# H-00488_-_I2C_Address.net
KiCad netlist of a schematic drawn in Altium Designer
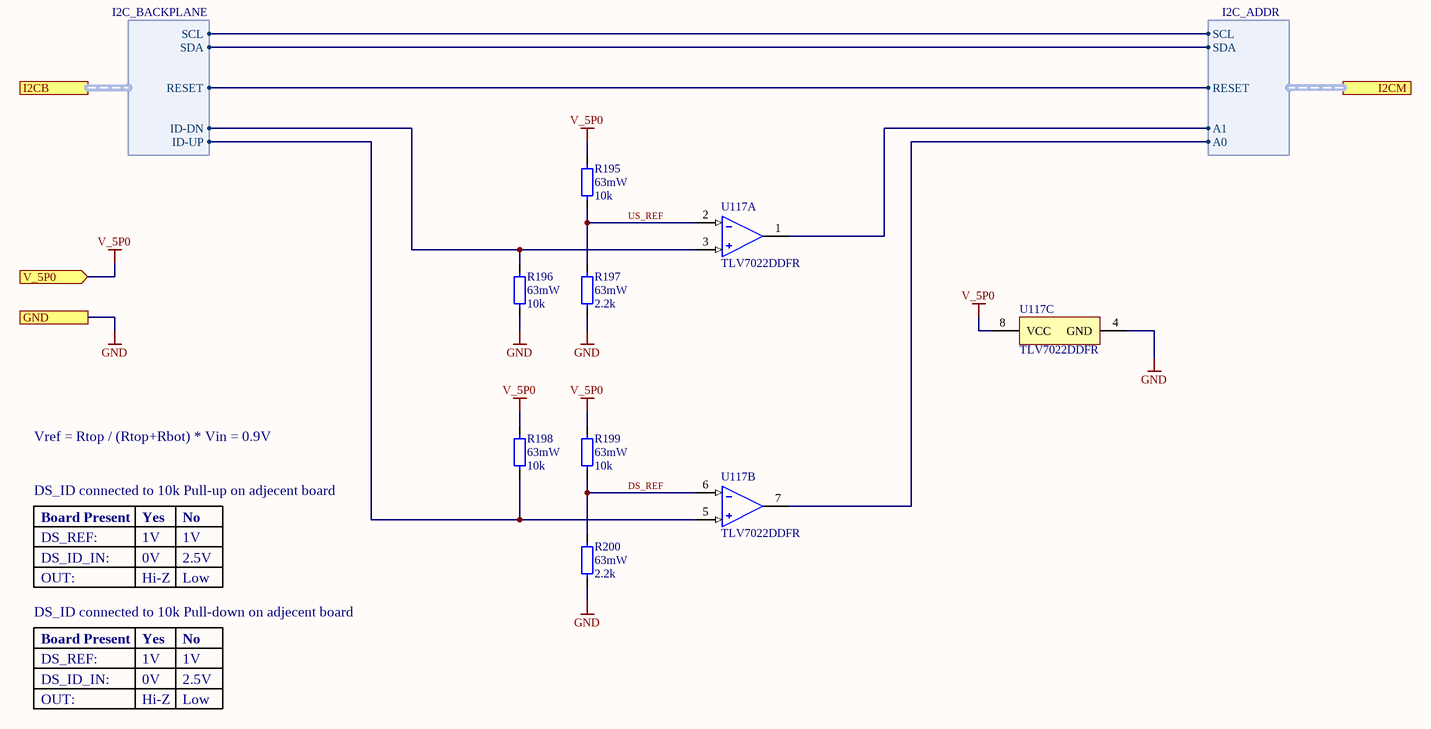
[diagram p0: H-00488 - I2C Address.SchDoc]

(export (version "E")
  (design (tool "Eeschema 10.0.6"))
  (components
    (comp (ref "R195")
      (value "10k")
      (footprint "RESC100X50X40L25N")
      (description "RES Standard Thick Film 0402 10K0 ±1% 0,063W")
      (fields
        (field (name "TOLERANCE") "1%")
        (field (name "RATED POWER") "63mW")
        (field (name "Comment") "CRCW040210K0FKED")
      )
      (libsource (lib "Hiber") (part "RESISTOR-2P"))
    )
    (comp (ref "R196")
      (value "10k")
      (footprint "RESC100X50X40L25N")
      (description "RES Standard Thick Film 0402 10K0 ±1% 0,063W")
      (fields
        (field (name "TOLERANCE") "1%")
        (field (name "RATED POWER") "63mW")
        (field (name "Comment") "CRCW040210K0FKED")
      )
      (libsource (lib "Hiber") (part "RESISTOR-2P"))
    )
    (comp (ref "R197")
      (value "2.2k")
      (footprint "RESC100X50X40L25N")
      (description "RES Standard Thick Film 0402 2K20 ±1% 0,063W")
      (fields
        (field (name "TOLERANCE") "1%")
        (field (name "RATED POWER") "63mW")
        (field (name "Comment") "CRCW04022K20FKED")
      )
      (libsource (lib "Hiber") (part "RESISTOR-2P"))
    )
    (comp (ref "R198")
      (value "10k")
      (footprint "RESC100X50X40L25N")
      (description "RES Standard Thick Film 0402 10K0 ±1% 0,063W")
      (fields
        (field (name "TOLERANCE") "1%")
        (field (name "RATED POWER") "63mW")
        (field (name "Comment") "CRCW040210K0FKED")
      )
      (libsource (lib "Hiber") (part "RESISTOR-2P"))
    )
    (comp (ref "R199")
      (value "10k")
      (footprint "RESC100X50X40L25N")
      (description "RES Standard Thick Film 0402 10K0 ±1% 0,063W")
      (fields
        (field (name "TOLERANCE") "1%")
        (field (name "RATED POWER") "63mW")
        (field (name "Comment") "CRCW040210K0FKED")
      )
      (libsource (lib "Hiber") (part "RESISTOR-2P"))
    )
    (comp (ref "R200")
      (value "2.2k")
      (footprint "RESC100X50X40L25N")
      (description "RES Standard Thick Film 0402 2K20 ±1% 0,063W")
      (fields
        (field (name "TOLERANCE") "1%")
        (field (name "RATED POWER") "63mW")
        (field (name "Comment") "CRCW04022K20FKED")
      )
      (libsource (lib "Hiber") (part "RESISTOR-2P"))
    )
    (comp (ref "U117")
      (value "TLV7022DDFR")
      (footprint "SOT23-8P65_280X110L45X30")
      (description "Micropower small size comparator (dual, open-drain output) 8-SOT-23-THIN -40 to 125")
      (libsource (lib "Hiber") (part "TLV7022DDFR"))
    )
  )
  (nets
    (net (code "3") (name "/A0") (class "Default")
      (node (ref "U117") (pin "7") (pinfunction "OUT_7") (pintype "open_collector"))
    )
    (net (code "4") (name "/A1") (class "Default")
      (node (ref "U117") (pin "1") (pinfunction "OUT_1") (pintype "open_collector"))
    )
    (net (code "5") (name "/DS_REF") (class "Default")
      (node (ref "R199") (pin "1") (pinfunction "1_1") (pintype "passive"))
      (node (ref "R200") (pin "2") (pinfunction "2_2") (pintype "passive"))
      (node (ref "U117") (pin "6") (pinfunction "IN-_6") (pintype "input"))
    )
    (net (code "6") (name "/ID-DN") (class "Default")
      (node (ref "R196") (pin "2") (pinfunction "2_2") (pintype "passive"))
      (node (ref "U117") (pin "3") (pinfunction "IN+_3") (pintype "input"))
    )
    (net (code "7") (name "/ID-UP") (class "Default")
      (node (ref "R198") (pin "1") (pinfunction "1_1") (pintype "passive"))
      (node (ref "U117") (pin "5") (pinfunction "IN+_5") (pintype "input"))
    )
    (net (code "11") (name "/US_REF") (class "Default")
      (node (ref "R195") (pin "1") (pinfunction "1_1") (pintype "passive"))
      (node (ref "R197") (pin "2") (pinfunction "2_2") (pintype "passive"))
      (node (ref "U117") (pin "2") (pinfunction "IN-_2") (pintype "input"))
    )
    (net (code "14") (name "GND") (class "Default")
      (node (ref "R196") (pin "1") (pinfunction "1_1") (pintype "passive"))
      (node (ref "R197") (pin "1") (pinfunction "1_1") (pintype "passive"))
      (node (ref "R200") (pin "1") (pinfunction "1_1") (pintype "passive"))
      (node (ref "U117") (pin "4") (pinfunction "GND_4") (pintype "power_in"))
    )
    (net (code "15") (name "V_5P0") (class "Default")
      (node (ref "R195") (pin "2") (pinfunction "2_2") (pintype "passive"))
      (node (ref "R198") (pin "2") (pinfunction "2_2") (pintype "passive"))
      (node (ref "R199") (pin "2") (pinfunction "2_2") (pintype "passive"))
      (node (ref "U117") (pin "8") (pinfunction "VCC_8") (pintype "power_in"))
    )
  )
)
